# arduino_Uno_Rev3-02-TH.net
KiCad netlist of a schematic drawn in EAGLE
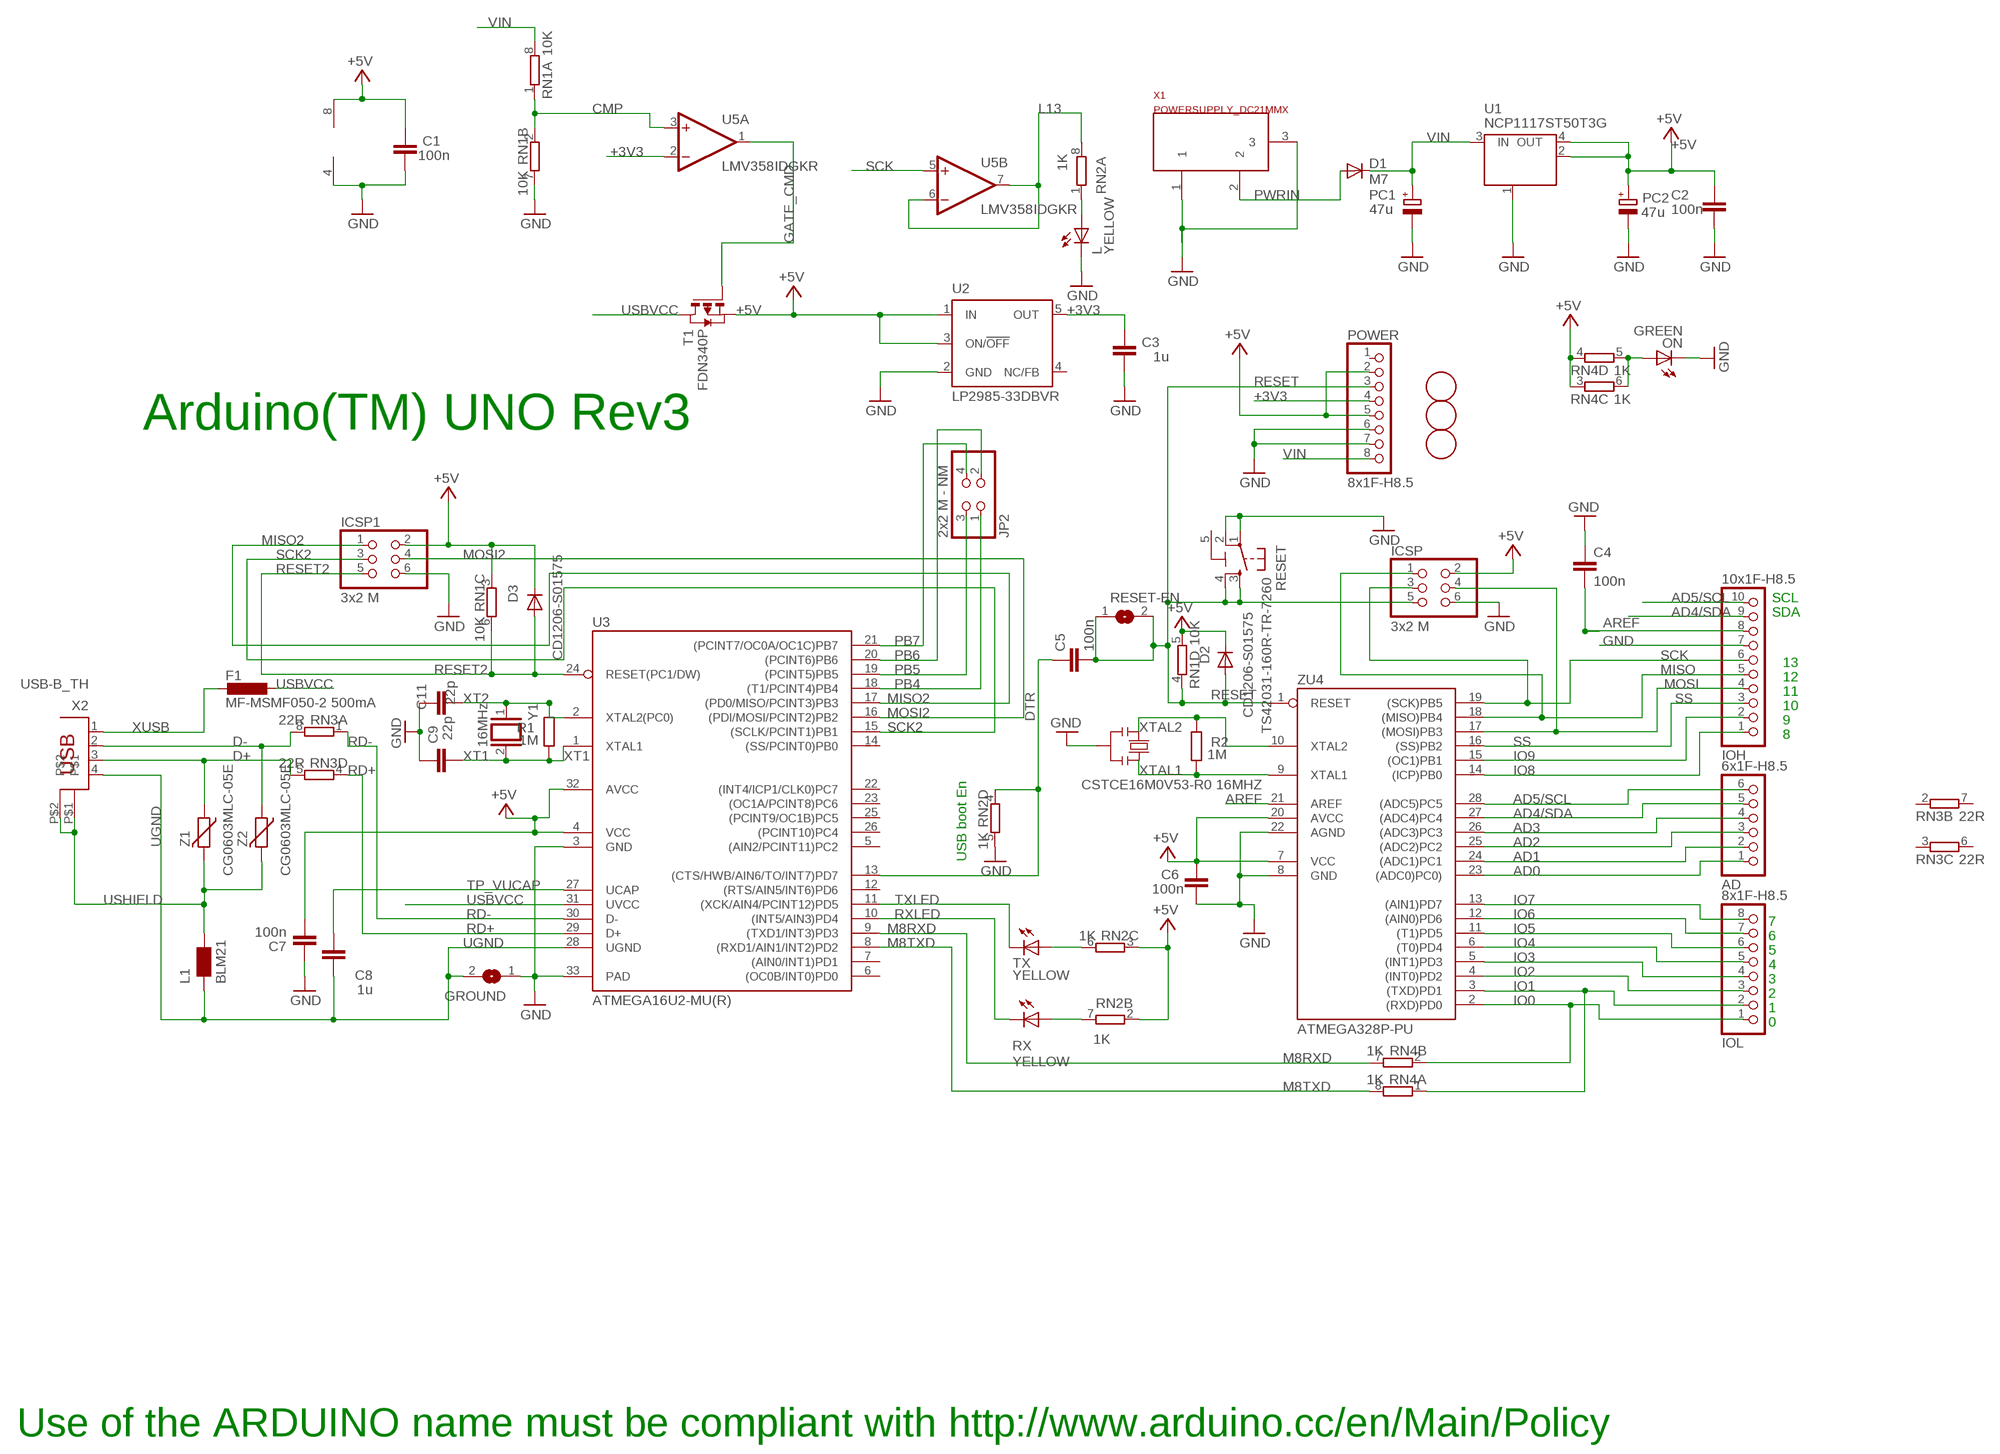
[diagram p0: schematic, sheet 1]

(export (version "E")
  (design (tool "Eeschema 10.0.6"))
  (components
    (comp (ref "AD")
      (value "6x1F-H8.5")
      (footprint "eagle-import:1X06")
      (libsource (lib "eagle-import") (part "PINHD-1X6"))
    )
    (comp (ref "C1")
      (value "100n")
      (footprint "eagle-import:C0603-ROUND")
      (libsource (lib "eagle-import") (part "C-EU0603-RND"))
    )
    (comp (ref "C2")
      (value "100n")
      (footprint "eagle-import:C0603-ROUND")
      (libsource (lib "eagle-import") (part "C-EU0603-RND"))
    )
    (comp (ref "C3")
      (value "1u")
      (footprint "eagle-import:C0603-ROUND")
      (libsource (lib "eagle-import") (part "C-EU0603-RND"))
    )
    (comp (ref "C4")
      (value "100n")
      (footprint "eagle-import:C0603-ROUND")
      (libsource (lib "eagle-import") (part "C-EU0603-RND"))
    )
    (comp (ref "C5")
      (value "100n")
      (footprint "eagle-import:C0603-ROUND")
      (libsource (lib "eagle-import") (part "C-EU0603-RND"))
    )
    (comp (ref "C6")
      (value "100n")
      (footprint "eagle-import:C0603-ROUND")
      (libsource (lib "eagle-import") (part "C-EU0603-RND"))
    )
    (comp (ref "C7")
      (value "100n")
      (footprint "eagle-import:C0603-ROUND")
      (libsource (lib "eagle-import") (part "C-EU0603-RND"))
    )
    (comp (ref "C8")
      (value "1u")
      (footprint "eagle-import:C0603-ROUND")
      (libsource (lib "eagle-import") (part "C-EU0603-RND"))
    )
    (comp (ref "C9")
      (value "22p")
      (footprint "eagle-import:C0603-ROUND")
      (libsource (lib "eagle-import") (part "C-EU0603-RND"))
    )
    (comp (ref "C11")
      (value "22p")
      (footprint "eagle-import:C0603-ROUND")
      (libsource (lib "eagle-import") (part "C-EU0603-RND"))
    )
    (comp (ref "D1")
      (value "M7")
      (footprint "eagle-import:SMB")
      (libsource (lib "eagle-import") (part "DIODE-SMB"))
    )
    (comp (ref "D2")
      (value "CD1206-S01575")
      (footprint "eagle-import:MINIMELF")
      (libsource (lib "eagle-import") (part "DIODE-MINIMELF"))
    )
    (comp (ref "D3")
      (value "CD1206-S01575")
      (footprint "eagle-import:MINIMELF")
      (libsource (lib "eagle-import") (part "DIODE-MINIMELF"))
    )
    (comp (ref "F1")
      (value "MF-MSMF050-2 500mA")
      (footprint "eagle-import:L1812")
      (libsource (lib "eagle-import") (part "L-EUL1812"))
    )
    (comp (ref "FD1")
      (value "FIDUCIALMOUNT")
      (footprint "eagle-import:FIDUCIA-MOUNT")
      (libsource (lib "eagle-import") (part "FIDUCIALMOUNT"))
    )
    (comp (ref "FD2")
      (value "FIDUCIALMOUNT")
      (footprint "eagle-import:FIDUCIA-MOUNT")
      (libsource (lib "eagle-import") (part "FIDUCIALMOUNT"))
    )
    (comp (ref "FD3")
      (value "FIDUCIALMOUNT")
      (footprint "eagle-import:FIDUCIA-MOUNT")
      (libsource (lib "eagle-import") (part "FIDUCIALMOUNT"))
    )
    (comp (ref "GROUND")
      (value "SJ")
      (footprint "eagle-import:SJ")
      (libsource (lib "eagle-import") (part "SJ"))
    )
    (comp (ref "ICSP")
      (value "3x2 M")
      (footprint "eagle-import:2X03")
      (libsource (lib "eagle-import") (part "PINHD-2X3"))
    )
    (comp (ref "ICSP1")
      (value "3x2 M")
      (footprint "eagle-import:2X03")
      (libsource (lib "eagle-import") (part "PINHD-2X3"))
    )
    (comp (ref "IOH")
      (value "10x1F-H8.5")
      (footprint "eagle-import:1X10")
      (libsource (lib "eagle-import") (part "PINHD-1X10_ARD"))
    )
    (comp (ref "IOL")
      (value "8x1F-H8.5")
      (footprint "eagle-import:1X08")
      (libsource (lib "eagle-import") (part "PINHD-1X8"))
    )
    (comp (ref "JP2")
      (value "2x2 M - NM")
      (footprint "eagle-import:2X02")
      (libsource (lib "eagle-import") (part "PINHD-2X2"))
    )
    (comp (ref "L")
      (value "YELLOW")
      (footprint "eagle-import:CHIP-LED0805")
      (libsource (lib "eagle-import") (part "LEDCHIP-LED0805"))
    )
    (comp (ref "L1")
      (value "BLM21")
      (footprint "eagle-import:0805")
      (libsource (lib "eagle-import") (part "WE-CBF_0805"))
    )
    (comp (ref "ON")
      (value "GREEN")
      (footprint "eagle-import:CHIP-LED0805")
      (libsource (lib "eagle-import") (part "LEDCHIP-LED0805"))
    )
    (comp (ref "PC1")
      (value "47u")
      (footprint "eagle-import:PANASONIC_D")
      (libsource (lib "eagle-import") (part "CPOL-EUD"))
    )
    (comp (ref "PC2")
      (value "47u")
      (footprint "eagle-import:PANASONIC_D")
      (libsource (lib "eagle-import") (part "CPOL-EUD"))
    )
    (comp (ref "POWER")
      (value "8x1F-H8.5")
      (footprint "eagle-import:1X08")
      (libsource (lib "eagle-import") (part "PINHD-1X8"))
    )
    (comp (ref "R1")
      (value "1M")
      (footprint "eagle-import:R0603-ROUND")
      (libsource (lib "eagle-import") (part "R-EU_R0603"))
    )
    (comp (ref "R2")
      (value "1M")
      (footprint "eagle-import:R0603-ROUND")
      (libsource (lib "eagle-import") (part "R-EU_R0603"))
    )
    (comp (ref "RESET")
      (value "TS42031-160R-TR-7260")
      (footprint "eagle-import:TS42")
      (libsource (lib "eagle-import") (part "TS42"))
    )
    (comp (ref "RESET-EN")
      (value "SJ")
      (footprint "eagle-import:SJ")
      (libsource (lib "eagle-import") (part "SJ"))
    )
    (comp (ref "RN1")
      (value "10K")
      (footprint "eagle-import:CAY16")
      (libsource (lib "eagle-import") (part "4R-NCAY16"))
    )
    (comp (ref "RN2")
      (value "1K")
      (footprint "eagle-import:CAY16")
      (libsource (lib "eagle-import") (part "4R-NCAY16"))
    )
    (comp (ref "RN3")
      (value "22R")
      (footprint "eagle-import:CAY16")
      (libsource (lib "eagle-import") (part "4R-NCAY16"))
    )
    (comp (ref "RN4")
      (value "1K")
      (footprint "eagle-import:CAY16")
      (libsource (lib "eagle-import") (part "4R-NCAY16"))
    )
    (comp (ref "RX")
      (value "YELLOW")
      (footprint "eagle-import:CHIP-LED0805")
      (libsource (lib "eagle-import") (part "LEDCHIP-LED0805"))
    )
    (comp (ref "T1")
      (value "FDN340P")
      (footprint "eagle-import:SOT-23")
      (libsource (lib "eagle-import") (part "PMOSSOT23"))
    )
    (comp (ref "TX")
      (value "YELLOW")
      (footprint "eagle-import:CHIP-LED0805")
      (libsource (lib "eagle-import") (part "LEDCHIP-LED0805"))
    )
    (comp (ref "U1")
      (value "NCP1117ST50T3G")
      (footprint "eagle-import:SOT223")
      (libsource (lib "eagle-import") (part "MC33269ST-3.3T3"))
    )
    (comp (ref "U2")
      (value "LP2985-33DBVR")
      (footprint "eagle-import:SOT23-DBV")
      (libsource (lib "eagle-import") (part "LP2985-XXDBVR33"))
    )
    (comp (ref "U3")
      (value "ATMEGA16U2-MU(R)")
      (footprint "eagle-import:MLF32")
      (libsource (lib "eagle-import") (part "ATMEGA16U2-MU"))
    )
    (comp (ref "U5")
      (value "LMV358IDGKR")
      (footprint "eagle-import:MSOP08")
      (libsource (lib "eagle-import") (part "LMV358?MMX"))
    )
    (comp (ref "X1")
      (value "POWERSUPPLY_DC21MMX")
      (footprint "eagle-import:POWERSUPPLY_DC-21MM")
      (libsource (lib "eagle-import") (part "POWERSUPPLY_DC21MMX"))
    )
    (comp (ref "X2")
      (value "USB-B_TH")
      (footprint "eagle-import:PN61729")
      (libsource (lib "eagle-import") (part "PN61729"))
    )
    (comp (ref "Y1")
      (value "16MHz")
      (footprint "eagle-import:QS")
      (libsource (lib "eagle-import") (part "XTAL/S"))
    )
    (comp (ref "Y2")
      (value "CSTCE16M0V53-R0 16MHZ")
      (footprint "eagle-import:RESONATOR")
      (libsource (lib "eagle-import") (part "RESONATORMU"))
    )
    (comp (ref "Z1")
      (value "CG0603MLC-05E")
      (footprint "eagle-import:CT_CN0603")
      (libsource (lib "eagle-import") (part "VARISTORCN0603"))
    )
    (comp (ref "Z2")
      (value "CG0603MLC-05E")
      (footprint "eagle-import:CT_CN0603")
      (libsource (lib "eagle-import") (part "VARISTORCN0603"))
    )
    (comp (ref "ZU4")
      (value "ATMEGA328P-PU")
      (footprint "eagle-import:DIL28-3")
      (libsource (lib "eagle-import") (part "ATMEGA328P-PU"))
    )
  )
  (nets
    (net (code "1") (name "+5V") (class "Default")
      (node (ref "C1") (pin "2") (pinfunction "2_2") (pintype "passive"))
      (node (ref "C2") (pin "2") (pinfunction "2_2") (pintype "passive"))
      (node (ref "C6") (pin "2") (pinfunction "2_2") (pintype "passive"))
      (node (ref "C7") (pin "1") (pinfunction "1_1") (pintype "passive"))
      (node (ref "D2") (pin "C") (pinfunction "C_C") (pintype "passive"))
      (node (ref "D3") (pin "C") (pinfunction "C_C") (pintype "passive"))
      (node (ref "ICSP") (pin "2") (pinfunction "2_2") (pintype "passive"))
      (node (ref "ICSP1") (pin "2") (pinfunction "2_2") (pintype "passive"))
      (node (ref "PC2") (pin "+") (pinfunction "+_+") (pintype "passive"))
      (node (ref "POWER") (pin "2") (pinfunction "2_2") (pintype "passive"))
      (node (ref "POWER") (pin "5") (pinfunction "5_5") (pintype "passive"))
      (node (ref "RN1") (pin "3") (pinfunction "1_3") (pintype "passive"))
      (node (ref "RN1") (pin "5") (pinfunction "2_5") (pintype "passive"))
      (node (ref "RN2") (pin "2") (pinfunction "1_2") (pintype "passive"))
      (node (ref "RN2") (pin "3") (pinfunction "1_3") (pintype "passive"))
      (node (ref "RN4") (pin "3") (pinfunction "1_3") (pintype "passive"))
      (node (ref "RN4") (pin "4") (pinfunction "1_4") (pintype "passive"))
      (node (ref "T1") (pin "2") (pinfunction "S_2") (pintype "passive"))
      (node (ref "U1") (pin "2") (pinfunction "OUT_2") (pintype "passive"))
      (node (ref "U1") (pin "4") (pinfunction "OUT_4") (pintype "passive"))
      (node (ref "U2") (pin "1") (pinfunction "IN_1") (pintype "input"))
      (node (ref "U2") (pin "3") (pinfunction "ON/~{OFF}_3") (pintype "input"))
      (node (ref "U3") (pin "32") (pinfunction "AVCC_32") (pintype "power_in"))
      (node (ref "U3") (pin "4") (pinfunction "VCC_4") (pintype "power_in"))
      (node (ref "U5") (pin "8") (pinfunction "V+_8") (pintype "power_in"))
      (node (ref "ZU4") (pin "20") (pinfunction "AVCC_20") (pintype "power_in"))
      (node (ref "ZU4") (pin "7") (pinfunction "VCC_7") (pintype "power_in"))
    )
    (net (code "2") (name "/+3V3") (class "Default")
      (node (ref "C3") (pin "2") (pinfunction "2_2") (pintype "passive"))
      (node (ref "POWER") (pin "4") (pinfunction "4_4") (pintype "passive"))
      (node (ref "U2") (pin "5") (pinfunction "OUT_5") (pintype "passive"))
      (node (ref "U5") (pin "2") (pinfunction "-IN_2") (pintype "input"))
    )
    (net (code "3") (name "/5-GND") (class "Default")
      (node (ref "RESET") (pin "5") (pinfunction "5-GND_5") (pintype "power_in"))
    )
    (net (code "4") (name "/AD0") (class "Default")
      (node (ref "AD") (pin "1") (pinfunction "1_1") (pintype "passive"))
      (node (ref "ZU4") (pin "23") (pinfunction "(ADC0)PC0)_23") (pintype "bidirectional"))
    )
    (net (code "5") (name "/AD1") (class "Default")
      (node (ref "AD") (pin "2") (pinfunction "2_2") (pintype "passive"))
      (node (ref "ZU4") (pin "24") (pinfunction "(ADC1)PC1_24") (pintype "bidirectional"))
    )
    (net (code "6") (name "/AD2") (class "Default")
      (node (ref "AD") (pin "3") (pinfunction "3_3") (pintype "passive"))
      (node (ref "ZU4") (pin "25") (pinfunction "(ADC2)PC2_25") (pintype "bidirectional"))
    )
    (net (code "7") (name "/AD3") (class "Default")
      (node (ref "AD") (pin "4") (pinfunction "4_4") (pintype "passive"))
      (node (ref "ZU4") (pin "26") (pinfunction "(ADC3)PC3_26") (pintype "bidirectional"))
    )
    (net (code "8") (name "/AD4{slash}SDA") (class "Default")
      (node (ref "AD") (pin "5") (pinfunction "5_5") (pintype "passive"))
      (node (ref "IOH") (pin "9") (pinfunction "9_9") (pintype "passive"))
      (node (ref "ZU4") (pin "27") (pinfunction "(ADC4)PC4_27") (pintype "bidirectional"))
    )
    (net (code "9") (name "/AD5{slash}SCL") (class "Default")
      (node (ref "AD") (pin "6") (pinfunction "6_6") (pintype "passive"))
      (node (ref "IOH") (pin "10") (pinfunction "10_10") (pintype "passive"))
      (node (ref "ZU4") (pin "28") (pinfunction "(ADC5)PC5_28") (pintype "bidirectional"))
    )
    (net (code "10") (name "/AREF") (class "Default")
      (node (ref "C4") (pin "2") (pinfunction "2_2") (pintype "passive"))
      (node (ref "IOH") (pin "8") (pinfunction "8_8") (pintype "passive"))
      (node (ref "ZU4") (pin "21") (pinfunction "AREF_21") (pintype "passive"))
    )
    (net (code "11") (name "/CMP") (class "Default")
      (node (ref "RN1") (pin "1") (pinfunction "1_1") (pintype "passive"))
      (node (ref "RN1") (pin "2") (pinfunction "1_2") (pintype "passive"))
      (node (ref "U5") (pin "3") (pinfunction "+IN_3") (pintype "input"))
    )
    (net (code "12") (name "/D+") (class "Default")
      (node (ref "RN3") (pin "5") (pinfunction "2_5") (pintype "passive"))
      (node (ref "X2") (pin "3") (pinfunction "3_3") (pintype "bidirectional"))
      (node (ref "Z1") (pin "1") (pinfunction "1_1") (pintype "passive"))
    )
    (net (code "13") (name "/D-") (class "Default")
      (node (ref "RN3") (pin "8") (pinfunction "2_8") (pintype "passive"))
      (node (ref "X2") (pin "2") (pinfunction "2_2") (pintype "bidirectional"))
      (node (ref "Z2") (pin "1") (pinfunction "1_1") (pintype "passive"))
    )
    (net (code "14") (name "/DTR") (class "Default")
      (node (ref "C5") (pin "1") (pinfunction "1_1") (pintype "passive"))
      (node (ref "RN2") (pin "4") (pinfunction "1_4") (pintype "passive"))
      (node (ref "U3") (pin "13") (pinfunction "(CTS/HWB/AIN6/TO/INT7)PD7_13") (pintype "bidirectional"))
    )
    (net (code "15") (name "/GATE_CMD") (class "Default")
      (node (ref "T1") (pin "3") (pinfunction "G_3") (pintype "passive"))
      (node (ref "U5") (pin "1") (pinfunction "OUT_1") (pintype "output"))
    )
    (net (code "16") (name "/IO0") (class "Default")
      (node (ref "IOL") (pin "1") (pinfunction "1_1") (pintype "passive"))
      (node (ref "RN4") (pin "2") (pinfunction "1_2") (pintype "passive"))
      (node (ref "ZU4") (pin "2") (pinfunction "(RXD)PD0_2") (pintype "bidirectional"))
    )
    (net (code "17") (name "/IO1") (class "Default")
      (node (ref "IOL") (pin "2") (pinfunction "2_2") (pintype "passive"))
      (node (ref "RN4") (pin "1") (pinfunction "1_1") (pintype "passive"))
      (node (ref "ZU4") (pin "3") (pinfunction "(TXD)PD1_3") (pintype "bidirectional"))
    )
    (net (code "18") (name "/IO2") (class "Default")
      (node (ref "IOL") (pin "3") (pinfunction "3_3") (pintype "passive"))
      (node (ref "ZU4") (pin "4") (pinfunction "(INT0)PD2_4") (pintype "bidirectional"))
    )
    (net (code "19") (name "/IO3") (class "Default")
      (node (ref "IOL") (pin "4") (pinfunction "4_4") (pintype "passive"))
      (node (ref "ZU4") (pin "5") (pinfunction "(INT1)PD3_5") (pintype "bidirectional"))
    )
    (net (code "20") (name "/IO4") (class "Default")
      (node (ref "IOL") (pin "5") (pinfunction "5_5") (pintype "passive"))
      (node (ref "ZU4") (pin "6") (pinfunction "(T0)PD4_6") (pintype "bidirectional"))
    )
    (net (code "21") (name "/IO5") (class "Default")
      (node (ref "IOL") (pin "6") (pinfunction "6_6") (pintype "passive"))
      (node (ref "ZU4") (pin "11") (pinfunction "(T1)PD5_11") (pintype "bidirectional"))
    )
    (net (code "22") (name "/IO6") (class "Default")
      (node (ref "IOL") (pin "7") (pinfunction "7_7") (pintype "passive"))
      (node (ref "ZU4") (pin "12") (pinfunction "(AIN0)PD6_12") (pintype "bidirectional"))
    )
    (net (code "23") (name "/IO7") (class "Default")
      (node (ref "IOL") (pin "8") (pinfunction "8_8") (pintype "passive"))
      (node (ref "ZU4") (pin "13") (pinfunction "(AIN1)PD7_13") (pintype "bidirectional"))
    )
    (net (code "24") (name "/IO8") (class "Default")
      (node (ref "IOH") (pin "1") (pinfunction "1_1") (pintype "passive"))
      (node (ref "ZU4") (pin "14") (pinfunction "(ICP)PB0_14") (pintype "bidirectional"))
    )
    (net (code "25") (name "/IO9") (class "Default")
      (node (ref "IOH") (pin "2") (pinfunction "2_2") (pintype "passive"))
      (node (ref "ZU4") (pin "15") (pinfunction "(OC1)PB1_15") (pintype "bidirectional"))
    )
    (net (code "26") (name "/L13") (class "Default")
      (node (ref "RN2") (pin "8") (pinfunction "2_8") (pintype "passive"))
      (node (ref "U5") (pin "6") (pinfunction "-IN_6") (pintype "input"))
      (node (ref "U5") (pin "7") (pinfunction "OUT_7") (pintype "output"))
    )
    (net (code "27") (name "/M8RXD") (class "Default")
      (node (ref "RN4") (pin "7") (pinfunction "2_7") (pintype "passive"))
      (node (ref "U3") (pin "9") (pinfunction "(TXD1/INT3)PD3_9") (pintype "bidirectional"))
    )
    (net (code "28") (name "/M8TXD") (class "Default")
      (node (ref "RN4") (pin "8") (pinfunction "2_8") (pintype "passive"))
      (node (ref "U3") (pin "8") (pinfunction "(RXD1/AIN1/INT2)PD2_8") (pintype "bidirectional"))
    )
    (net (code "29") (name "/MISO") (class "Default")
      (node (ref "ICSP") (pin "1") (pinfunction "1_1") (pintype "passive"))
      (node (ref "IOH") (pin "5") (pinfunction "5_5") (pintype "passive"))
      (node (ref "ZU4") (pin "18") (pinfunction "(MISO)PB4_18") (pintype "bidirectional"))
    )
    (net (code "30") (name "/MISO2") (class "Default")
      (node (ref "ICSP1") (pin "1") (pinfunction "1_1") (pintype "passive"))
      (node (ref "U3") (pin "17") (pinfunction "(PD0/MISO/PCINT3)PB3_17") (pintype "bidirectional"))
    )
    (net (code "31") (name "/MOSI") (class "Default")
      (node (ref "ICSP") (pin "4") (pinfunction "4_4") (pintype "passive"))
      (node (ref "IOH") (pin "4") (pinfunction "4_4") (pintype "passive"))
      (node (ref "ZU4") (pin "17") (pinfunction "(MOSI)PB3_17") (pintype "bidirectional"))
    )
    (net (code "32") (name "/MOSI2") (class "Default")
      (node (ref "ICSP1") (pin "4") (pinfunction "4_4") (pintype "passive"))
      (node (ref "U3") (pin "16") (pinfunction "(PDI/MOSI/PCINT2)PB2_16") (pintype "bidirectional"))
    )
    (net (code "33") (name "/PB4") (class "Default")
      (node (ref "JP2") (pin "1") (pinfunction "1_1") (pintype "passive"))
      (node (ref "U3") (pin "18") (pinfunction "(T1/PCINT4)PB4_18") (pintype "bidirectional"))
    )
    (net (code "34") (name "/PB5") (class "Default")
      (node (ref "JP2") (pin "3") (pinfunction "3_3") (pintype "passive"))
      (node (ref "U3") (pin "19") (pinfunction "(PCINT5)PB5_19") (pintype "bidirectional"))
    )
    (net (code "35") (name "/PB6") (class "Default")
      (node (ref "JP2") (pin "2") (pinfunction "2_2") (pintype "passive"))
      (node (ref "U3") (pin "20") (pinfunction "(PCINT6)PB6_20") (pintype "bidirectional"))
    )
    (net (code "36") (name "/PB7") (class "Default")
      (node (ref "JP2") (pin "4") (pinfunction "4_4") (pintype "passive"))
      (node (ref "U3") (pin "21") (pinfunction "(PCINT7/OC0A/OC1C)PB7_21") (pintype "bidirectional"))
    )
    (net (code "37") (name "/PWRIN") (class "Default")
      (node (ref "D1") (pin "A") (pinfunction "A_A") (pintype "passive"))
      (node (ref "X1") (pin "2") (pinfunction "2_2") (pintype "power_in"))
    )
    (net (code "38") (name "/RD+") (class "Default")
      (node (ref "RN3") (pin "4") (pinfunction "1_4") (pintype "passive"))
      (node (ref "U3") (pin "29") (pinfunction "D+_29") (pintype "bidirectional"))
    )
    (net (code "39") (name "/RD-") (class "Default")
      (node (ref "RN3") (pin "1") (pinfunction "1_1") (pintype "passive"))
      (node (ref "U3") (pin "30") (pinfunction "D-_30") (pintype "bidirectional"))
    )
    (net (code "40") (name "/RESET") (class "Default")
      (node (ref "C5") (pin "2") (pinfunction "2_2") (pintype "passive"))
      (node (ref "D2") (pin "A") (pinfunction "A_A") (pintype "passive"))
      (node (ref "ICSP") (pin "5") (pinfunction "5_5") (pintype "passive"))
      (node (ref "POWER") (pin "3") (pinfunction "3_3") (pintype "passive"))
      (node (ref "RESET") (pin "3") (pinfunction "3_3") (pintype "passive"))
      (node (ref "RESET") (pin "4") (pinfunction "4_4") (pintype "passive"))
      (node (ref "RESET-EN") (pin "1") (pinfunction "1_1") (pintype "passive"))
      (node (ref "RESET-EN") (pin "2") (pinfunction "2_2") (pintype "passive"))
      (node (ref "RN1") (pin "4") (pinfunction "1_4") (pintype "passive"))
      (node (ref "ZU4") (pin "1") (pinfunction "RESET_1") (pintype "input"))
    )
    (net (code "41") (name "/RESET2") (class "Default")
      (node (ref "D3") (pin "A") (pinfunction "A_A") (pintype "passive"))
      (node (ref "ICSP1") (pin "5") (pinfunction "5_5") (pintype "passive"))
      (node (ref "RN1") (pin "6") (pinfunction "2_6") (pintype "passive"))
      (node (ref "U3") (pin "24") (pinfunction "RESET(PC1/DW)_24") (pintype "input"))
    )
    (net (code "42") (name "/RXLED") (class "Default")
      (node (ref "RX") (pin "C") (pinfunction "C_C") (pintype "passive"))
      (node (ref "U3") (pin "10") (pinfunction "(INT5/AIN3)PD4_10") (pintype "bidirectional"))
    )
    (net (code "43") (name "/SCK") (class "Default")
      (node (ref "ICSP") (pin "3") (pinfunction "3_3") (pintype "passive"))
      (node (ref "IOH") (pin "6") (pinfunction "6_6") (pintype "passive"))
      (node (ref "U5") (pin "5") (pinfunction "+IN_5") (pintype "input"))
      (node (ref "ZU4") (pin "19") (pinfunction "(SCK)PB5_19") (pintype "bidirectional"))
    )
    (net (code "44") (name "/SCK2") (class "Default")
      (node (ref "ICSP1") (pin "3") (pinfunction "3_3") (pintype "passive"))
      (node (ref "U3") (pin "15") (pinfunction "(SCLK/PCINT1)PB1_15") (pintype "bidirectional"))
    )
    (net (code "45") (name "/SS") (class "Default")
      (node (ref "IOH") (pin "3") (pinfunction "3_3") (pintype "passive"))
      (node (ref "ZU4") (pin "16") (pinfunction "(SS)PB2_16") (pintype "bidirectional"))
    )
    (net (code "46") (name "/TP_VUCAP") (class "Default")
      (node (ref "C8") (pin "1") (pinfunction "1_1") (pintype "passive"))
      (node (ref "U3") (pin "27") (pinfunction "UCAP_27") (pintype "passive"))
    )
    (net (code "47") (name "/TXLED") (class "Default")
      (node (ref "TX") (pin "C") (pinfunction "C_C") (pintype "passive"))
      (node (ref "U3") (pin "11") (pinfunction "(XCK/AIN4/PCINT12)PD5_11") (pintype "bidirectional"))
    )
    (net (code "48") (name "/UGND") (class "Default")
      (node (ref "C8") (pin "2") (pinfunction "2_2") (pintype "passive"))
      (node (ref "GROUND") (pin "2") (pinfunction "2_2") (pintype "passive"))
      (node (ref "L1") (pin "1") (pinfunction "1_1") (pintype "passive"))
      (node (ref "U3") (pin "28") (pinfunction "UGND_28") (pintype "power_in"))
      (node (ref "X2") (pin "4") (pinfunction "4_4") (pintype "bidirectional"))
    )
    (net (code "49") (name "/USBVCC") (class "Default")
      (node (ref "F1") (pin "1") (pinfunction "1_1") (pintype "passive"))
      (node (ref "T1") (pin "1") (pinfunction "D_1") (pintype "passive"))
      (node (ref "U3") (pin "31") (pinfunction "UVCC_31") (pintype "power_in"))
    )
    (net (code "50") (name "/USHIELD") (class "Default")
      (node (ref "L1") (pin "2") (pinfunction "2_2") (pintype "passive"))
      (node (ref "X2") (pin "P$1") (pinfunction "P$1_P$1") (pintype "bidirectional"))
      (node (ref "X2") (pin "P$2") (pinfunction "P$2_P$2") (pintype "bidirectional"))
      (node (ref "Z1") (pin "2") (pinfunction "2_2") (pintype "passive"))
      (node (ref "Z2") (pin "2") (pinfunction "2_2") (pintype "passive"))
    )
    (net (code "51") (name "/VIN") (class "Default")
      (node (ref "D1") (pin "C") (pinfunction "C_C") (pintype "passive"))
      (node (ref "PC1") (pin "+") (pinfunction "+_+") (pintype "passive"))
      (node (ref "POWER") (pin "8") (pinfunction "8_8") (pintype "passive"))
      (node (ref "RN1") (pin "8") (pinfunction "2_8") (pintype "passive"))
      (node (ref "U1") (pin "3") (pinfunction "IN_3") (pintype "input"))
    )
    (net (code "52") (name "/XT1") (class "Default")
      (node (ref "C9") (pin "1") (pinfunction "1_1") (pintype "passive"))
      (node (ref "R1") (pin "1") (pinfunction "1_1") (pintype "passive"))
      (node (ref "U3") (pin "1") (pinfunction "XTAL1_1") (pintype "bidirectional"))
      (node (ref "Y1") (pin "2") (pinfunction "2_2") (pintype "passive"))
    )
    (net (code "53") (name "/XT2") (class "Default")
      (node (ref "C11") (pin "1") (pinfunction "1_1") (pintype "passive"))
      (node (ref "R1") (pin "2") (pinfunction "2_2") (pintype "passive"))
      (node (ref "U3") (pin "2") (pinfunction "XTAL2(PC0)_2") (pintype "bidirectional"))
      (node (ref "Y1") (pin "1") (pinfunction "1_1") (pintype "passive"))
    )
    (net (code "54") (name "/XTAL1") (class "Default")
      (node (ref "R2") (pin "1") (pinfunction "1_1") (pintype "passive"))
      (node (ref "Y2") (pin "3") (pinfunction "3_3") (pintype "passive"))
      (node (ref "ZU4") (pin "9") (pinfunction "XTAL1_9") (pintype "bidirectional"))
    )
    (net (code "55") (name "/XTAL2") (class "Default")
      (node (ref "R2") (pin "2") (pinfunction "2_2") (pintype "passive"))
      (node (ref "Y2") (pin "1") (pinfunction "1_1") (pintype "passive"))
      (node (ref "ZU4") (pin "10") (pinfunction "XTAL2_10") (pintype "bidirectional"))
    )
    (net (code "56") (name "/XUSB") (class "Default")
      (node (ref "F1") (pin "2") (pinfunction "2_2") (pintype "passive"))
      (node (ref "X2") (pin "1") (pinfunction "1_1") (pintype "bidirectional"))
    )
    (net (code "57") (name "GND") (class "Default")
      (node (ref "C1") (pin "1") (pinfunction "1_1") (pintype "passive"))
      (node (ref "C11") (pin "2") (pinfunction "2_2") (pintype "passive"))
      (node (ref "C2") (pin "1") (pinfunction "1_1") (pintype "passive"))
      (node (ref "C3") (pin "1") (pinfunction "1_1") (pintype "passive"))
      (node (ref "C4") (pin "1") (pinfunction "1_1") (pintype "passive"))
      (node (ref "C6") (pin "1") (pinfunction "1_1") (pintype "passive"))
      (node (ref "C7") (pin "2") (pinfunction "2_2") (pintype "passive"))
      (node (ref "C9") (pin "2") (pinfunction "2_2") (pintype "passive"))
      (node (ref "GROUND") (pin "1") (pinfunction "1_1") (pintype "passive"))
      (node (ref "ICSP") (pin "6") (pinfunction "6_6") (pintype "passive"))
      (node (ref "ICSP1") (pin "6") (pinfunction "6_6") (pintype "passive"))
      (node (ref "IOH") (pin "7") (pinfunction "7_7") (pintype "passive"))
      (node (ref "L") (pin "C") (pinfunction "C_C") (pintype "passive"))
      (node (ref "ON") (pin "C") (pinfunction "C_C") (pintype "passive"))
      (node (ref "PC1") (pin "-") (pinfunction "-_-") (pintype "passive"))
      (node (ref "PC2") (pin "-") (pinfunction "-_-") (pintype "passive"))
      (node (ref "POWER") (pin "6") (pinfunction "6_6") (pintype "passive"))
      (node (ref "POWER") (pin "7") (pinfunction "7_7") (pintype "passive"))
      (node (ref "RESET") (pin "1") (pinfunction "1_1") (pintype "passive"))
      (node (ref "RESET") (pin "2") (pinfunction "2_2") (pintype "passive"))
      (node (ref "RN1") (pin "7") (pinfunction "2_7") (pintype "passive"))
      (node (ref "RN2") (pin "5") (pinfunction "2_5") (pintype "passive"))
      (node (ref "U1") (pin "1") (pinfunction "GND/ADJ_1") (pintype "input"))
      (node (ref "U2") (pin "2") (pinfunction "GND_2") (pintype "power_in"))
      (node (ref "U3") (pin "3") (pinfunction "GND_3") (pintype "power_in"))
      (node (ref "U3") (pin "33") (pinfunction "PAD_33") (pintype "power_in"))
      (node (ref "U5") (pin "4") (pinfunction "V-_4") (pintype "power_in"))
      (node (ref "X1") (pin "1") (pinfunction "1_1") (pintype "power_in"))
      (node (ref "X1") (pin "3") (pinfunction "3_3") (pintype "power_in"))
      (node (ref "Y2") (pin "2") (pinfunction "2_2") (pintype "passive"))
      (node (ref "ZU4") (pin "22") (pinfunction "AGND_22") (pintype "power_in"))
      (node (ref "ZU4") (pin "8") (pinfunction "GND_8") (pintype "power_in"))
    )
    (net (code "58") (name "Net-(L-PadA)") (class "Default")
      (node (ref "L") (pin "A") (pinfunction "A_A") (pintype "passive"))
      (node (ref "RN2") (pin "1") (pinfunction "1_1") (pintype "passive"))
    )
    (net (code "59") (name "Net-(RN2B-2)") (class "Default")
      (node (ref "RN2") (pin "7") (pinfunction "2_7") (pintype "passive"))
      (node (ref "RX") (pin "A") (pinfunction "A_A") (pintype "passive"))
    )
    (net (code "60") (name "Net-(RN2C-2)") (class "Default")
      (node (ref "RN2") (pin "6") (pinfunction "2_6") (pintype "passive"))
      (node (ref "TX") (pin "A") (pinfunction "A_A") (pintype "passive"))
    )
    (net (code "61") (name "Net-(RN4C-2)") (class "Default")
      (node (ref "ON") (pin "A") (pinfunction "A_A") (pintype "passive"))
      (node (ref "RN4") (pin "5") (pinfunction "2_5") (pintype "passive"))
      (node (ref "RN4") (pin "6") (pinfunction "2_6") (pintype "passive"))
    )
    (net (code "62") (name "unconnected-(POWER-Pad1)") (class "Default")
      (node (ref "POWER") (pin "1") (pinfunction "1_1") (pintype "passive"))
    )
    (net (code "63") (name "unconnected-(RN3B-1-Pad2)") (class "Default")
      (node (ref "RN3") (pin "2") (pinfunction "1_2") (pintype "passive"))
    )
    (net (code "64") (name "unconnected-(RN3B-2-Pad7)") (class "Default")
      (node (ref "RN3") (pin "7") (pinfunction "2_7") (pintype "passive"))
    )
    (net (code "65") (name "unconnected-(RN3C-1-Pad3)") (class "Default")
      (node (ref "RN3") (pin "3") (pinfunction "1_3") (pintype "passive"))
    )
    (net (code "66") (name "unconnected-(RN3C-2-Pad6)") (class "Default")
      (node (ref "RN3") (pin "6") (pinfunction "2_6") (pintype "passive"))
    )
    (net (code "67") (name "unconnected-(U2-NC{slash}FB-Pad4)") (class "Default")
      (node (ref "U2") (pin "4") (pinfunction "NC/FB_4") (pintype "passive"))
    )
    (net (code "68") (name "unconnected-(U3-(AIN0{slash}INT1)PD1-Pad7)") (class "Default")
      (node (ref "U3") (pin "7") (pinfunction "(AIN0/INT1)PD1_7") (pintype "bidirectional"))
    )
    (net (code "69") (name "unconnected-(U3-(AIN2{slash}PCINT11)PC2-Pad5)") (class "Default")
      (node (ref "U3") (pin "5") (pinfunction "(AIN2/PCINT11)PC2_5") (pintype "bidirectional"))
    )
    (net (code "70") (name "unconnected-(U3-(INT4{slash}ICP1{slash}CLK0)PC7-Pad22)") (class "Default")
      (node (ref "U3") (pin "22") (pinfunction "(INT4/ICP1/CLK0)PC7_22") (pintype "bidirectional"))
    )
    (net (code "71") (name "unconnected-(U3-(OC0B{slash}INT0)PD0-Pad6)") (class "Default")
      (node (ref "U3") (pin "6") (pinfunction "(OC0B/INT0)PD0_6") (pintype "bidirectional"))
    )
    (net (code "72") (name "unconnected-(U3-(OC1A{slash}PCINT8)PC6-Pad23)") (class "Default")
      (node (ref "U3") (pin "23") (pinfunction "(OC1A/PCINT8)PC6_23") (pintype "bidirectional"))
    )
    (net (code "73") (name "unconnected-(U3-(PCINT9{slash}OC1B)PC5-Pad25)") (class "Default")
      (node (ref "U3") (pin "25") (pinfunction "(PCINT9/OC1B)PC5_25") (pintype "bidirectional"))
    )
    (net (code "74") (name "unconnected-(U3-(PCINT10)PC4-Pad26)") (class "Default")
      (node (ref "U3") (pin "26") (pinfunction "(PCINT10)PC4_26") (pintype "bidirectional"))
    )
    (net (code "75") (name "unconnected-(U3-(RTS{slash}AIN5{slash}INT6)PD6-Pad12)") (class "Default")
      (node (ref "U3") (pin "12") (pinfunction "(RTS/AIN5/INT6)PD6_12") (pintype "bidirectional"))
    )
    (net (code "76") (name "unconnected-(U3-(SS{slash}PCINT0)PB0-Pad14)") (class "Default")
      (node (ref "U3") (pin "14") (pinfunction "(SS/PCINT0)PB0_14") (pintype "bidirectional"))
    )
  )
)
